# IncubaLibre.net
KiCad netlist of a schematic drawn in EAGLE
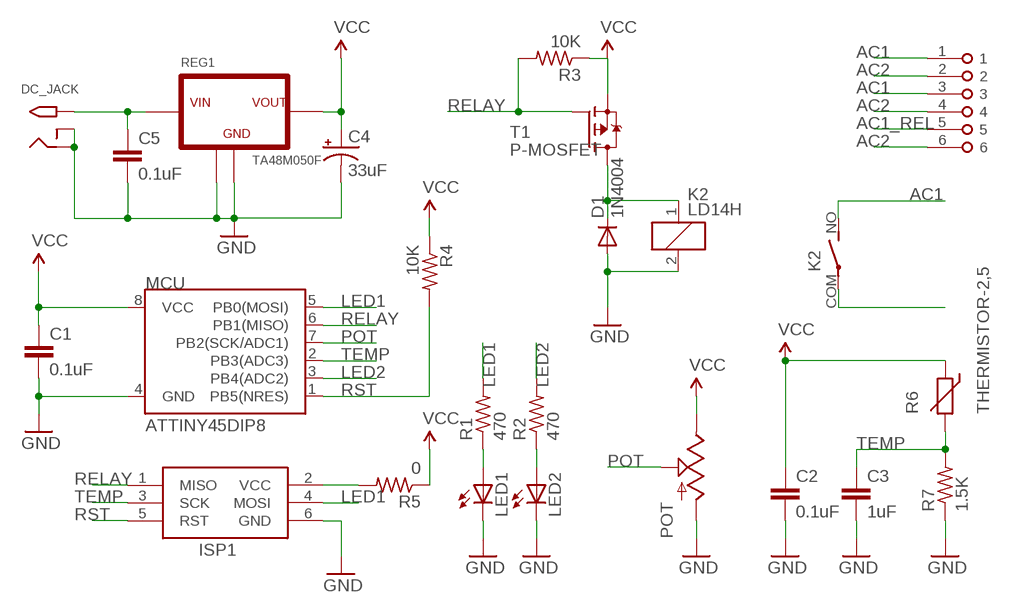
[diagram p0: schematic, sheet 1]

(export (version "E")
  (design (tool "Eeschema 10.0.6"))
  (components
    (comp (ref "AC")
      (value "TERMINAL-6")
      (footprint "eagle-import:MBE-156")
      (libsource (lib "eagle-import") (part "TERMINAL-6"))
    )
    (comp (ref "C1")
      (value "0.1uF")
      (footprint "eagle-import:CAP-PTH-SMALL")
      (libsource (lib "eagle-import") (part "CAPPTH"))
    )
    (comp (ref "C2")
      (value "0.1uF")
      (footprint "eagle-import:CAP-PTH-SMALL")
      (libsource (lib "eagle-import") (part "CAPPTH"))
    )
    (comp (ref "C3")
      (value "1uF")
      (footprint "eagle-import:CAP-PTH-SMALL")
      (libsource (lib "eagle-import") (part "CAPPTH"))
    )
    (comp (ref "C4")
      (value "33uF")
      (footprint "eagle-import:CPOL-RADIAL-10UF-25V")
      (libsource (lib "eagle-import") (part "CAP_POLPTH2"))
    )
    (comp (ref "C5")
      (value "0.1uF")
      (footprint "eagle-import:CAP-PTH-SMALL")
      (libsource (lib "eagle-import") (part "CAPPTH"))
    )
    (comp (ref "D1")
      (value "1N4004")
      (footprint "eagle-import:DO41-10")
      (libsource (lib "eagle-import") (part "1N4004"))
    )
    (comp (ref "DC_JACK")
      (value "2.1MMJACKTHM")
      (footprint "eagle-import:PJ-102A")
      (libsource (lib "eagle-import") (part "2.1MMJACKTHM"))
    )
    (comp (ref "ISP1")
      (value "AVRISP-6")
      (footprint "eagle-import:AVRISP")
      (libsource (lib "eagle-import") (part "AVRISP-6"))
    )
    (comp (ref "K2")
      (value "LD14H")
      (footprint "eagle-import:LD")
      (libsource (lib "eagle-import") (part "LD?14H"))
    )
    (comp (ref "LED1")
      (value "LED5MM")
      (footprint "eagle-import:LED5MM")
      (libsource (lib "eagle-import") (part "LED5MM"))
    )
    (comp (ref "LED2")
      (value "LED5MM")
      (footprint "eagle-import:LED5MM")
      (libsource (lib "eagle-import") (part "LED5MM"))
    )
    (comp (ref "MCU")
      (value "ATTINY45DIP8")
      (footprint "eagle-import:DIP08")
      (libsource (lib "eagle-import") (part "ATTINY45DIP8"))
    )
    (comp (ref "POT")
      (value "POTTRIM")
      (footprint "eagle-import:TRIM_POT")
      (libsource (lib "eagle-import") (part "POTTRIM"))
    )
    (comp (ref "R1")
      (value "470")
      (footprint "eagle-import:0204_7")
      (libsource (lib "eagle-import") (part "R-US_0204/7"))
    )
    (comp (ref "R2")
      (value "470")
      (footprint "eagle-import:0204_7")
      (libsource (lib "eagle-import") (part "R-US_0204/7"))
    )
    (comp (ref "R3")
      (value "10K")
      (footprint "eagle-import:0204_7")
      (libsource (lib "eagle-import") (part "R-US_0204/7"))
    )
    (comp (ref "R4")
      (value "10K")
      (footprint "eagle-import:0204_7")
      (libsource (lib "eagle-import") (part "R-US_0204/7"))
    )
    (comp (ref "R5")
      (value "0")
      (footprint "eagle-import:0204_7")
      (libsource (lib "eagle-import") (part "R-US_0204/7"))
    )
    (comp (ref "R6")
      (value "THERMISTOR-2,5")
      (footprint "eagle-import:RS-2,5")
      (libsource (lib "eagle-import") (part "THERMISTOR-2,5"))
    )
    (comp (ref "R7")
      (value "1.5K")
      (footprint "eagle-import:0204_7")
      (libsource (lib "eagle-import") (part "R-US_0204/7"))
    )
    (comp (ref "REG1")
      (value "TA48M050F")
      (footprint "eagle-import:TO-220")
      (libsource (lib "eagle-import") (part "REGULATOR-TO-220"))
    )
    (comp (ref "T1")
      (value "P-MOSFET")
      (footprint "eagle-import:TO92-")
      (libsource (lib "eagle-import") (part "P-MOSFET"))
    )
  )
  (nets
    (net (code "1") (name "/AC1") (class "Default")
      (node (ref "AC") (pin "1") (pinfunction "1_1") (pintype "bidirectional"))
      (node (ref "AC") (pin "3") (pinfunction "3_3") (pintype "bidirectional"))
      (node (ref "K2") (pin "NO") (pinfunction "S_NO") (pintype "passive"))
    )
    (net (code "2") (name "/AC1_REL") (class "Default")
      (node (ref "AC") (pin "5") (pinfunction "5_5") (pintype "bidirectional"))
      (node (ref "K2") (pin "COM") (pinfunction "P_COM") (pintype "passive"))
    )
    (net (code "3") (name "/AC2") (class "Default")
      (node (ref "AC") (pin "2") (pinfunction "2_2") (pintype "bidirectional"))
      (node (ref "AC") (pin "4") (pinfunction "4_4") (pintype "bidirectional"))
      (node (ref "AC") (pin "6") (pinfunction "6_6") (pintype "bidirectional"))
    )
    (net (code "4") (name "/LED1") (class "Default")
      (node (ref "ISP1") (pin "4") (pinfunction "MOSI_4") (pintype "output"))
      (node (ref "MCU") (pin "5") (pinfunction "PB0(MOSI)_5") (pintype "bidirectional"))
      (node (ref "R1") (pin "2") (pinfunction "2_2") (pintype "passive"))
    )
    (net (code "5") (name "/LED2") (class "Default")
      (node (ref "MCU") (pin "3") (pinfunction "PB4(ADC2)_3") (pintype "bidirectional"))
      (node (ref "R2") (pin "2") (pinfunction "2_2") (pintype "passive"))
    )
    (net (code "6") (name "/POT") (class "Default")
      (node (ref "MCU") (pin "7") (pinfunction "PB2(SCK/ADC1)_7") (pintype "bidirectional"))
      (node (ref "POT") (pin "1") (pinfunction "S_1") (pintype "passive"))
    )
    (net (code "7") (name "/RELAY") (class "Default")
      (node (ref "ISP1") (pin "1") (pinfunction "MISO_1") (pintype "input"))
      (node (ref "MCU") (pin "6") (pinfunction "PB1(MISO)_6") (pintype "bidirectional"))
      (node (ref "R3") (pin "2") (pinfunction "2_2") (pintype "passive"))
      (node (ref "T1") (pin "2") (pinfunction "G_2") (pintype "passive"))
    )
    (net (code "8") (name "/RST") (class "Default")
      (node (ref "ISP1") (pin "5") (pinfunction "RST_5") (pintype "output"))
      (node (ref "MCU") (pin "1") (pinfunction "PB5(NRES)_1") (pintype "bidirectional"))
      (node (ref "R4") (pin "2") (pinfunction "2_2") (pintype "passive"))
    )
    (net (code "9") (name "/TEMP") (class "Default")
      (node (ref "C3") (pin "1") (pinfunction "1_1") (pintype "passive"))
      (node (ref "ISP1") (pin "3") (pinfunction "SCK_3") (pintype "output"))
      (node (ref "MCU") (pin "2") (pinfunction "PB3(ADC3)_2") (pintype "bidirectional"))
      (node (ref "R6") (pin "2") (pinfunction "2_2") (pintype "passive"))
      (node (ref "R7") (pin "2") (pinfunction "2_2") (pintype "passive"))
    )
    (net (code "10") (name "GND") (class "Default")
      (node (ref "C1") (pin "2") (pinfunction "2_2") (pintype "passive"))
      (node (ref "C2") (pin "2") (pinfunction "2_2") (pintype "passive"))
      (node (ref "C3") (pin "2") (pinfunction "2_2") (pintype "passive"))
      (node (ref "C4") (pin "2") (pinfunction "-_2") (pintype "passive"))
      (node (ref "C5") (pin "2") (pinfunction "2_2") (pintype "passive"))
      (node (ref "D1") (pin "A") (pinfunction "A_A") (pintype "passive"))
      (node (ref "DC_JACK") (pin "RING") (pinfunction "RING_RING") (pintype "bidirectional"))
      (node (ref "DC_JACK") (pin "RING_SW") (pinfunction "RING_SW_RING_SW") (pintype "bidirectional"))
      (node (ref "ISP1") (pin "6") (pinfunction "GND_6") (pintype "power_in"))
      (node (ref "K2") (pin "2") (pinfunction "2_2") (pintype "passive"))
      (node (ref "LED1") (pin "K") (pinfunction "C_K") (pintype "passive"))
      (node (ref "LED2") (pin "K") (pinfunction "C_K") (pintype "passive"))
      (node (ref "MCU") (pin "4") (pinfunction "GND_4") (pintype "bidirectional"))
      (node (ref "POT") (pin "3") (pinfunction "A_3") (pintype "passive"))
      (node (ref "R7") (pin "1") (pinfunction "1_1") (pintype "passive"))
      (node (ref "REG1") (pin "CENTER") (pinfunction "GND_CENTER") (pintype "power_in"))
      (node (ref "REG1") (pin "THERMAL") (pinfunction "GND_THERMAL") (pintype "power_in"))
    )
    (net (code "11") (name "Net-(ISP1-VCC)") (class "Default")
      (node (ref "ISP1") (pin "2") (pinfunction "VCC_2") (pintype "power_in"))
      (node (ref "R5") (pin "2") (pinfunction "2_2") (pintype "passive"))
    )
    (net (code "12") (name "Net-(LED1-PadA)") (class "Default")
      (node (ref "LED1") (pin "A") (pinfunction "A_A") (pintype "passive"))
      (node (ref "R1") (pin "1") (pinfunction "1_1") (pintype "passive"))
    )
    (net (code "13") (name "Net-(LED2-PadA)") (class "Default")
      (node (ref "LED2") (pin "A") (pinfunction "A_A") (pintype "passive"))
      (node (ref "R2") (pin "1") (pinfunction "1_1") (pintype "passive"))
    )
    (net (code "14") (name "Net-(REG1-VIN)") (class "Default")
      (node (ref "C5") (pin "1") (pinfunction "1_1") (pintype "passive"))
      (node (ref "DC_JACK") (pin "TIP") (pinfunction "TIP_TIP") (pintype "bidirectional"))
      (node (ref "REG1") (pin "LEFT") (pinfunction "VIN_LEFT") (pintype "input"))
    )
    (net (code "15") (name "Net-(T1-D)") (class "Default")
      (node (ref "D1") (pin "C") (pinfunction "C_C") (pintype "passive"))
      (node (ref "K2") (pin "1") (pinfunction "1_1") (pintype "passive"))
      (node (ref "T1") (pin "1") (pinfunction "D_1") (pintype "passive"))
    )
    (net (code "16") (name "VCC") (class "Default")
      (node (ref "C1") (pin "1") (pinfunction "1_1") (pintype "passive"))
      (node (ref "C2") (pin "1") (pinfunction "1_1") (pintype "passive"))
      (node (ref "C4") (pin "1") (pinfunction "+_1") (pintype "passive"))
      (node (ref "MCU") (pin "8") (pinfunction "VCC_8") (pintype "bidirectional"))
      (node (ref "POT") (pin "2") (pinfunction "E_2") (pintype "passive"))
      (node (ref "R3") (pin "1") (pinfunction "1_1") (pintype "passive"))
      (node (ref "R4") (pin "1") (pinfunction "1_1") (pintype "passive"))
      (node (ref "R5") (pin "1") (pinfunction "1_1") (pintype "passive"))
      (node (ref "R6") (pin "1") (pinfunction "1_1") (pintype "passive"))
      (node (ref "REG1") (pin "RIGHT") (pinfunction "VOUT_RIGHT") (pintype "power_in"))
      (node (ref "T1") (pin "3") (pinfunction "S_3") (pintype "passive"))
    )
  )
)
